# Pressure_Sensor_Breakout_Rev_2.net
KiCad netlist of a schematic drawn in Altium Designer
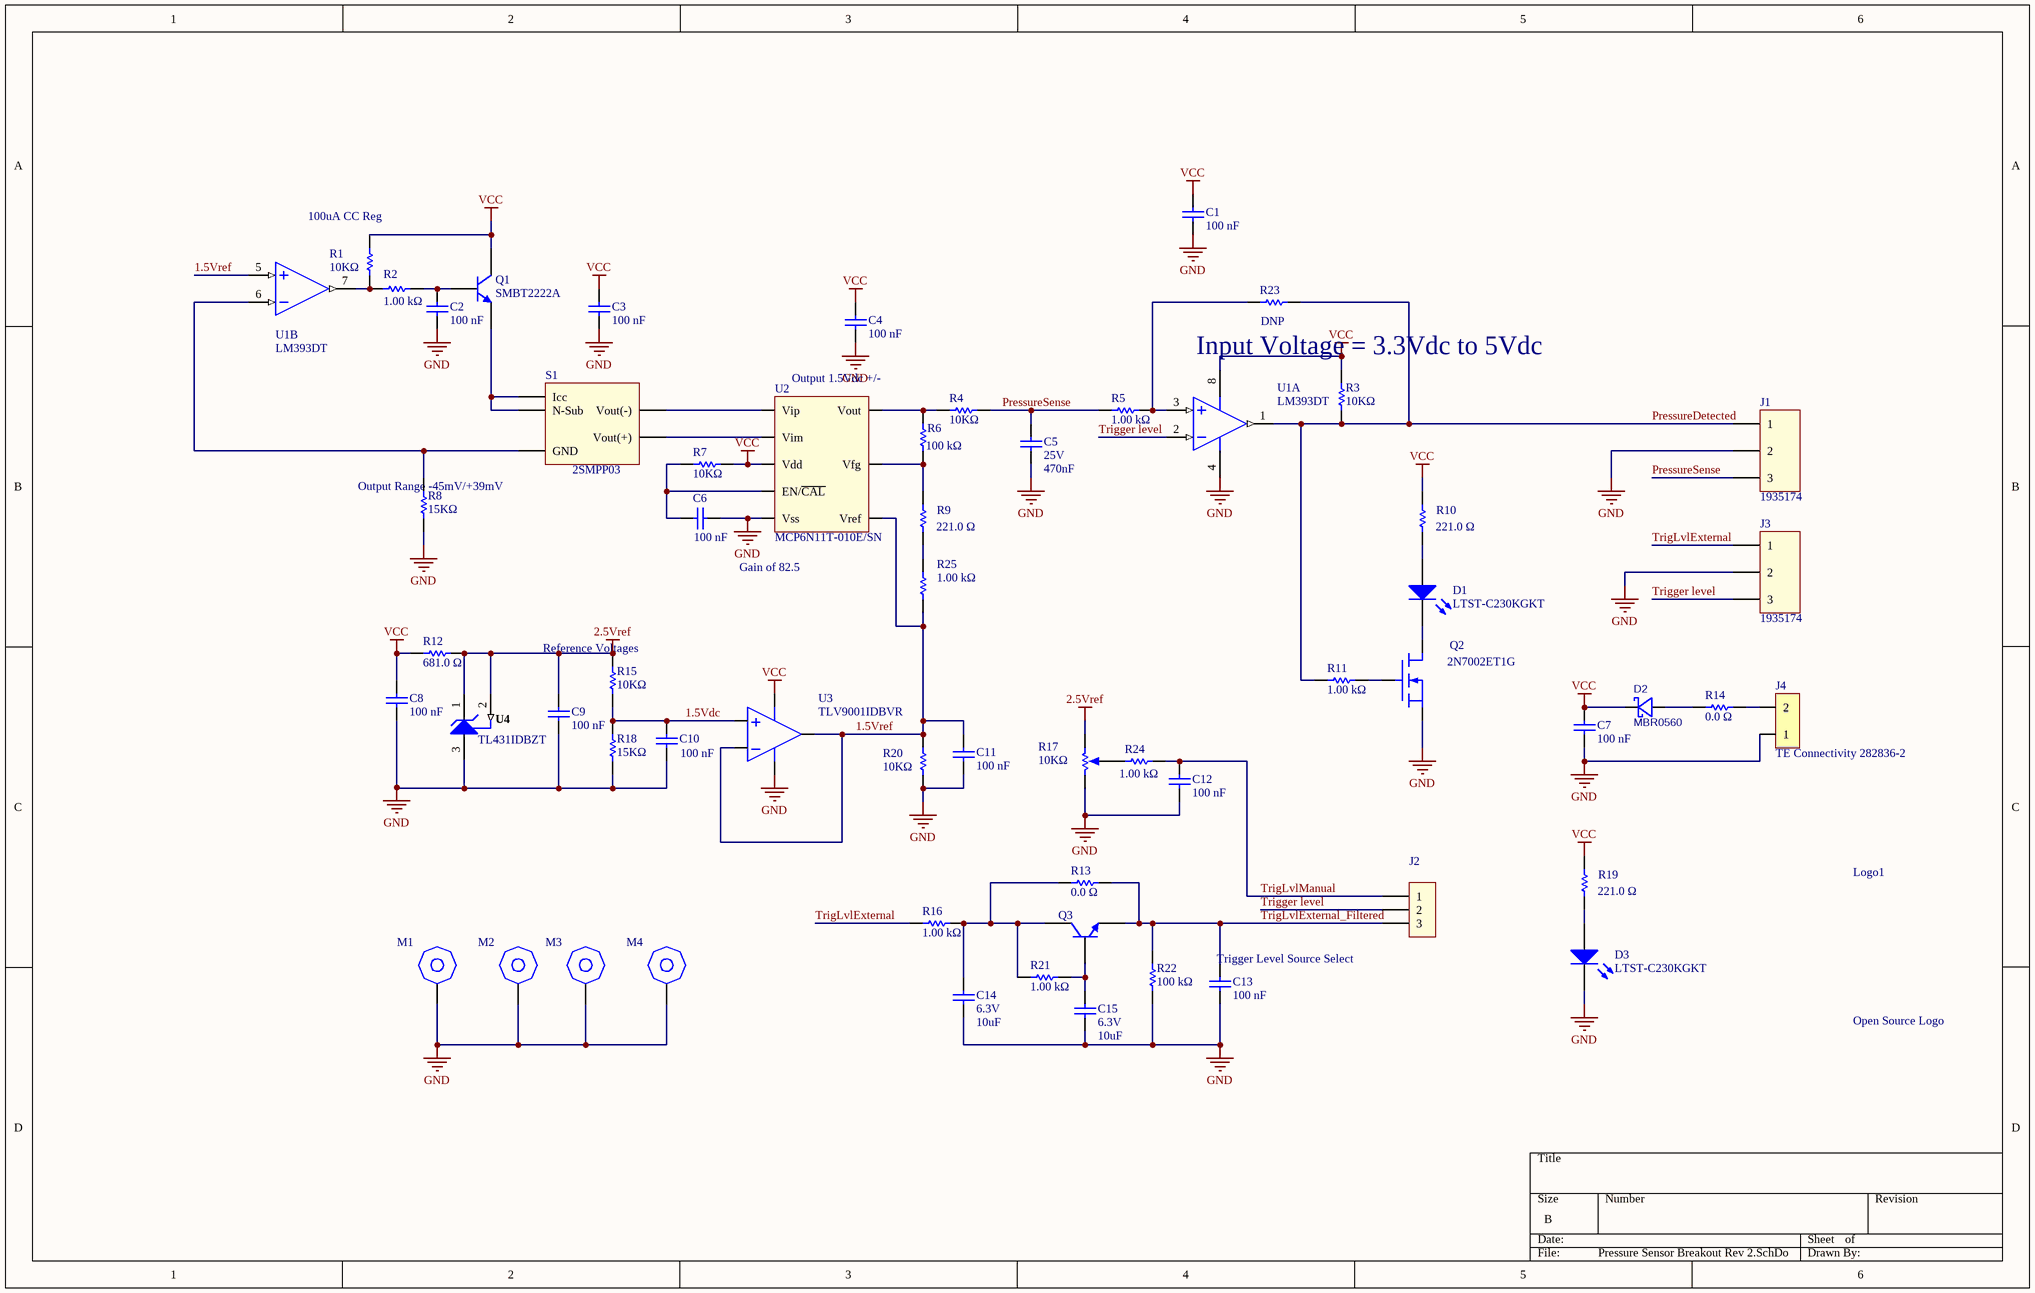
[diagram p0: Pressure Sensor Breakout Rev 2.SchDoc]

(export (version "E")
  (design (tool "Eeschema 10.0.6"))
  (components
    (comp (ref "C1")
      (value "08055C104JAT2A")
      (footprint "Cap,0805")
      (description "Capacitor; Ceramic; Cap 0.1 uF; Tol 5%; Vol-Rtg 50 VDC; SMT; 0805; X7R; Tape & Reel")
      (fields (field (name "CAPACITANCE") "100 nF"))
      (libsource (lib "Master JULY2019") (part "Cap,0805,100nf,50V,5%,08055C104JAT2A"))
    )
    (comp (ref "C2")
      (value "08055C104JAT2A")
      (footprint "Cap,0805")
      (description "Capacitor; Ceramic; Cap 0.1 uF; Tol 5%; Vol-Rtg 50 VDC; SMT; 0805; X7R; Tape & Reel")
      (fields (field (name "CAPACITANCE") "100 nF"))
      (libsource (lib "Master JULY2019") (part "Cap,0805,100nf,50V,5%,08055C104JAT2A"))
    )
    (comp (ref "C3")
      (value "08055C104JAT2A")
      (footprint "Cap,0805")
      (description "Capacitor; Ceramic; Cap 0.1 uF; Tol 5%; Vol-Rtg 50 VDC; SMT; 0805; X7R; Tape & Reel")
      (fields (field (name "CAPACITANCE") "100 nF"))
      (libsource (lib "Master JULY2019") (part "Cap,0805,100nf,50V,5%,08055C104JAT2A"))
    )
    (comp (ref "C4")
      (value "08055C104JAT2A")
      (footprint "Cap,0805")
      (description "Capacitor; Ceramic; Cap 0.1 uF; Tol 5%; Vol-Rtg 50 VDC; SMT; 0805; X7R; Tape & Reel")
      (fields (field (name "CAPACITANCE") "100 nF"))
      (libsource (lib "Master JULY2019") (part "Cap,0805,100nf,50V,5%,08055C104JAT2A"))
    )
    (comp (ref "C5")
      (value "CGA4J2X7R1E474K125AA")
      (footprint "Cap,0805")
      (description "0.47µF ±10% 25V Ceramic Capacitor X7R 0805 (2012 Metric)")
      (fields
        (field (name "MANUFACTURER") "TDK Corporation")
        (field (name "VOLTAGE RATING (DC)") "25V")
        (field (name "CAPACITANCE") "470nF")
      )
      (libsource (lib "Master Nov2021") (part "Cap,0805,470nf,25V,10%,CGA4J2X7R1E474K125AA"))
    )
    (comp (ref "C6")
      (value "08055C104JAT2A")
      (footprint "Cap,0805")
      (description "Capacitor; Ceramic; Cap 0.1 uF; Tol 5%; Vol-Rtg 50 VDC; SMT; 0805; X7R; Tape & Reel")
      (fields (field (name "CAPACITANCE") "100 nF"))
      (libsource (lib "Master JULY2019") (part "Cap,0805,100nf,50V,5%,08055C104JAT2A"))
    )
    (comp (ref "C7")
      (value "08055C104JAT2A")
      (footprint "Cap,0805")
      (description "Capacitor; Ceramic; Cap 0.1 uF; Tol 5%; Vol-Rtg 50 VDC; SMT; 0805; X7R; Tape & Reel")
      (fields (field (name "CAPACITANCE") "100 nF"))
      (libsource (lib "Master JULY2019") (part "Cap,0805,100nf,50V,5%,08055C104JAT2A"))
    )
    (comp (ref "C8")
      (value "08055C104JAT2A")
      (footprint "Cap,0805")
      (description "Capacitor; Ceramic; Cap 0.1 uF; Tol 5%; Vol-Rtg 50 VDC; SMT; 0805; X7R; Tape & Reel")
      (fields (field (name "CAPACITANCE") "100 nF"))
      (libsource (lib "Master JULY2019") (part "Cap,0805,100nf,50V,5%,08055C104JAT2A"))
    )
    (comp (ref "C9")
      (value "08055C104JAT2A")
      (footprint "Cap,0805")
      (description "Capacitor; Ceramic; Cap 0.1 uF; Tol 5%; Vol-Rtg 50 VDC; SMT; 0805; X7R; Tape & Reel")
      (fields (field (name "CAPACITANCE") "100 nF"))
      (libsource (lib "Master JULY2019") (part "Cap,0805,100nf,50V,5%,08055C104JAT2A"))
    )
    (comp (ref "C10")
      (value "08055C104JAT2A")
      (footprint "Cap,0805")
      (description "Capacitor; Ceramic; Cap 0.1 uF; Tol 5%; Vol-Rtg 50 VDC; SMT; 0805; X7R; Tape & Reel")
      (fields (field (name "CAPACITANCE") "100 nF"))
      (libsource (lib "Master JULY2019") (part "Cap,0805,100nf,50V,5%,08055C104JAT2A"))
    )
    (comp (ref "C11")
      (value "08055C104JAT2A")
      (footprint "Cap,0805")
      (description "Capacitor; Ceramic; Cap 0.1 uF; Tol 5%; Vol-Rtg 50 VDC; SMT; 0805; X7R; Tape & Reel")
      (fields (field (name "CAPACITANCE") "100 nF"))
      (libsource (lib "Master JULY2019") (part "Cap,0805,100nf,50V,5%,08055C104JAT2A"))
    )
    (comp (ref "C12")
      (value "08055C104JAT2A")
      (footprint "Cap,0805")
      (description "Capacitor; Ceramic; Cap 0.1 uF; Tol 5%; Vol-Rtg 50 VDC; SMT; 0805; X7R; Tape & Reel")
      (fields (field (name "CAPACITANCE") "100 nF"))
      (libsource (lib "Master JULY2019") (part "Cap,0805,100nf,50V,5%,08055C104JAT2A"))
    )
    (comp (ref "C13")
      (value "08055C104JAT2A")
      (footprint "Cap,0805")
      (description "Capacitor; Ceramic; Cap 0.1 uF; Tol 5%; Vol-Rtg 50 VDC; SMT; 0805; X7R; Tape & Reel")
      (fields (field (name "CAPACITANCE") "100 nF"))
      (libsource (lib "Master JULY2019") (part "Cap,0805,100nf,50V,5%,08055C104JAT2A"))
    )
    (comp (ref "C14")
      (value "Cap")
      (footprint "Cap,0805")
      (description "CL21 Series 10 uF 6.3V ±10 % Tolerance X5R SMT Multilayer Ceramic Capacitor")
      (fields
        (field (name "TOLERANCE") "±10%")
        (field (name "VOLTAGE - RATED") "6.3V")
        (field (name "CAPACITANCE") "10uF")
      )
      (libsource (lib "Master JUL_2019-Shawn") (part "Cap,0805,10uf,6.3V,10%,CL21A106KQFNNNG"))
    )
    (comp (ref "C15")
      (value "Cap")
      (footprint "Cap,0805")
      (description "CL21 Series 10 uF 6.3V ±10 % Tolerance X5R SMT Multilayer Ceramic Capacitor")
      (fields
        (field (name "TOLERANCE") "±10%")
        (field (name "VOLTAGE - RATED") "6.3V")
        (field (name "CAPACITANCE") "10uF")
      )
      (libsource (lib "Master JUL_2019-Shawn") (part "Cap,0805,10uf,6.3V,10%,CL21A106KQFNNNG"))
    )
    (comp (ref "D1")
      (value "LTST-C230KGKT")
      (footprint "LED,SMD,Bottom Entry,1206")
      (description "LED GREEN CLEAR CHIP SMD")
      (fields (field (name "MANUFACTURER") "Lite-On Inc."))
      (libsource (lib "Master DEC 2020") (part "LED,1206,Green,SMD,BtmEnt,LTST-C230KGKT"))
    )
    (comp (ref "D2")
      (value "MBR0560")
      (footprint "SOD123")
      (description "Dio,Sig,Schtky,0.5A,60V,SOD123")
      (fields (field (name "MANUFACTURER") "MCC") (field (name "VOLTAGE") "60V"))
      (libsource (lib "Master DEC 2020") (part "Diode,SOD123,Shottky,60V,0.5A,MBR0560"))
    )
    (comp (ref "D3")
      (value "LTST-C230KGKT")
      (footprint "LED,SMD,Bottom Entry,1206")
      (description "LED GREEN CLEAR CHIP SMD")
      (fields (field (name "MANUFACTURER") "Lite-On Inc."))
      (libsource (lib "Master DEC 2020") (part "LED,1206,Green,SMD,BtmEnt,LTST-C230KGKT"))
    )
    (comp (ref "J1")
      (value "1935174")
      (footprint "CONNECTOR,TerminalBlock,3 POS,1935174")
      (description "TERM BLK 3POS SIDE ENTRY 5MM PCB")
      (fields
        (field (name "MANUFACTURER") "Phoenix Contact")
        (field (name "VOLTAGE") "300V")
        (field (name "MFG P/N") "1935174")
      )
      (libsource (lib "Master DEC 2020") (part "Conn,TH,WireTerminal,3Pos,18A,300Vdc,1935174"))
    )
    (comp (ref "J2")
      (value "Generic Header")
      (footprint "Header,3POS,0.1\",Vert")
      (description "Generic Header 3 pos header 0.1\"")
      (libsource (lib "Master JULY2019") (part "Header 1x3,0.1{dblquote},TH,Generic"))
    )
    (comp (ref "J3")
      (value "1935174")
      (footprint "CONNECTOR,TerminalBlock,3 POS,1935174")
      (description "TERM BLK 3POS SIDE ENTRY 5MM PCB")
      (fields
        (field (name "MANUFACTURER") "Phoenix Contact")
        (field (name "VOLTAGE") "300V")
        (field (name "MFG P/N") "1935174")
      )
      (libsource (lib "Master DEC 2020") (part "Conn,TH,WireTerminal,3Pos,18A,300Vdc,1935174"))
    )
    (comp (ref "J4")
      (value "TE Connectivity 282836-2")
      (footprint "TERM BLOCK 2POS SIDE ENTRY 5MM")
      (description "Wire to Board 2 Position 5 mm Pitch 30-16 AWG Euro Style Terminal Block")
      (fields (field (name "MANUFACTURER PART NUMBER") "282836-2"))
      (libsource (lib "Master DEC 2020") (part "TERM BLOCK 2POS SIDE ENTRY 5MM, 282836-2"))
    )
    (comp (ref "Logo1")
      (value "Open Source Logo")
      (footprint "Symbol,Open Source")
      (description "Open Source Silk Screen Logo")
      (libsource (lib "Master Nov2021") (part "Symbol,Open Source"))
    )
    (comp (ref "M1")
      (value "M3 hex Standoff")
      (footprint "Standoff,Hex,M3,8mm")
      (description "HEX STANDOFF M3,generic")
      (libsource (lib "Master JULY2019") (part "Mech,Standoff, M3, Hex"))
    )
    (comp (ref "M2")
      (value "M3 hex Standoff")
      (footprint "Standoff,Hex,M3,8mm")
      (description "HEX STANDOFF M3,generic")
      (libsource (lib "Master JULY2019") (part "Mech,Standoff, M3, Hex"))
    )
    (comp (ref "M3")
      (value "M3 hex Standoff")
      (footprint "Standoff,Hex,M3,8mm")
      (description "HEX STANDOFF M3,generic")
      (libsource (lib "Master JULY2019") (part "Mech,Standoff, M3, Hex"))
    )
    (comp (ref "M4")
      (value "M3 hex Standoff")
      (footprint "Standoff,Hex,M3,8mm")
      (description "HEX STANDOFF M3,generic")
      (libsource (lib "Master JULY2019") (part "Mech,Standoff, M3, Hex"))
    )
    (comp (ref "Q1")
      (value "SMBT2222A")
      (footprint "SOT23-3")
      (description "NPN Silicon Switching Transistor, 40 V VCEO, 600 mA IC, SOT23, Reel, Green")
      (fields (field (name "MFG P/N") "SMBT2222A"))
      (libsource (lib "Master JULY2019") (part "Trans,40V,600mA,0.33W, SMBT2222A"))
    )
    (comp (ref "Q2")
      (value "2N7002ET1G")
      (footprint "SOT23-3")
      (description "Small Signal MOSFET, 60 V, 310 mA, Single, N-Channel, 3-Pin SOT-23, Pb-Free, Tape and Reel")
      (fields
        (field (name "MANUFACTURER") "ON Semiconductor")
        (field (name "MANUFACTURER PART NUMBER") "2N7002ET1G")
      )
      (libsource (lib "Master DEC 2020") (part "MOSFET,N-Channel,SOT23,0.25A,60V,2N7002ET1G"))
    )
    (comp (ref "Q3")
      (value "NPN")
      (footprint "SOT23-3")
      (description "NPN Silicon Switching Transistor, 40 V VCEO, 600 mA IC, SOT23, Reel, Green")
      (libsource (lib "Master JUL_2019-Shawn") (part "Trans,40V,600mA,0.33W, SMBT2222A"))
    )
    (comp (ref "R1")
      (value "Vishay / Dale CRCW080510K0FKTA")
      (footprint "res, 0805, HD")
      (description "RES SMD 10K OHM 1% 1/8W 0805")
      (fields (field (name "RESISTANCE") "10KΩ"))
      (libsource (lib "Master JULY2019") (part "Res,0805,10.0kΩ,1%,100 ppm,CRCW080510K0FKTA"))
    )
    (comp (ref "R2")
      (value "Vishay CRCW08051K00JNEA")
      (footprint "res, 0805, HD")
      (description "Res Thick Film 0805 1K Ohm 5% 0.125W(1/8W) ±200ppm/C Molded SMD Automotive Paper T/R")
      (fields
        (field (name "MANUFACTURER PART NUMBER") "CRCW08051K00JNEA")
        (field (name "RESISTANCE") "1.00 kΩ")
      )
      (libsource (lib "Master JULY2019") (part "Res,0805,1.00 kΩ,5%,200ppm,CRCW08051K00JNEA"))
    )
    (comp (ref "R3")
      (value "Vishay / Dale CRCW080510K0FKTA")
      (footprint "res, 0805, HD")
      (description "RES SMD 10K OHM 1% 1/8W 0805")
      (fields (field (name "RESISTANCE") "10KΩ"))
      (libsource (lib "Master JULY2019") (part "Res,0805,10.0kΩ,1%,100 ppm,CRCW080510K0FKTA"))
    )
    (comp (ref "R4")
      (value "Vishay / Dale CRCW080510K0FKTA")
      (footprint "res, 0805, HD")
      (description "RES SMD 10K OHM 1% 1/8W 0805")
      (fields (field (name "RESISTANCE") "10KΩ"))
      (libsource (lib "Master DEC 2020") (part "Res,0805,10.0kΩ,1%,100 ppm,CRCW080510K0FKTA"))
    )
    (comp (ref "R5")
      (value "Vishay CRCW08051K00JNEA")
      (footprint "res, 0805, HD")
      (description "Res Thick Film 0805 1K Ohm 5% 0.125W(1/8W) ±200ppm/C Molded SMD Automotive Paper T/R")
      (fields
        (field (name "MANUFACTURER PART NUMBER") "CRCW08051K00JNEA")
        (field (name "RESISTANCE") "1.00 kΩ")
      )
      (libsource (lib "Master JULY2019") (part "Res,0805,1.00 kΩ,5%,200ppm,CRCW08051K00JNEA"))
    )
    (comp (ref "R6")
      (value "CRCW0805100KFKEA")
      (footprint "res, 0805, HD")
      (description "100 kOhms ±1% 0.125W, 1/8W Chip Resistor 0805 (2012 Metric) Thick Film")
      (fields (field (name "MANUFACTURER") "Vishay") (field (name "RESISTANCE") "100 kΩ"))
      (libsource (lib "Master DEC 2020") (part "Res,0805,100kΩ,1%,100ppm,CRCW0805100KFKEA"))
    )
    (comp (ref "R7")
      (value "Vishay / Dale CRCW080510K0FKTA")
      (footprint "res, 0805, HD")
      (description "RES SMD 10K OHM 1% 1/8W 0805")
      (fields (field (name "RESISTANCE") "10KΩ"))
      (libsource (lib "Master JULY2019") (part "Res,0805,10.0kΩ,1%,100 ppm,CRCW080510K0FKTA"))
    )
    (comp (ref "R8")
      (value "CRGCQ0805F15K")
      (footprint "res, 0805, HD")
      (fields (field (name "TOLERANCE") "±1%") (field (name "RESISTANCE") "15KΩ"))
      (libsource (lib "Master JULY2019") (part "Res,0805,15KΩ,1%,±100ppm/°C,CRGCQ0805F15K"))
    )
    (comp (ref "R9")
      (value "Vishay Dale CRCW0805221RFKTA")
      (footprint "res, 0805, HD")
      (description "RES SMD 221 OHM 1% 1/8W 0805")
      (fields (field (name "RESISTANCE") "221.0 Ω"))
      (libsource (lib "Master DEC 2020") (part "Res,0805,221Ω,1%,100ppm,CRCW0805221RFKTA"))
    )
    (comp (ref "R10")
      (value "Vishay Dale CRCW0805221RFKTA")
      (footprint "res, 0805, HD")
      (description "RES SMD 221 OHM 1% 1/8W 0805")
      (fields (field (name "RESISTANCE") "221.0 Ω"))
      (libsource (lib "Master DEC 2020") (part "Res,0805,221Ω,1%,100ppm,CRCW0805221RFKTA"))
    )
    (comp (ref "R11")
      (value "Vishay CRCW08051K00JNEA")
      (footprint "res, 0805, HD")
      (description "Res Thick Film 0805 1K Ohm 5% 0.125W(1/8W) ±200ppm/C Molded SMD Automotive Paper T/R")
      (fields
        (field (name "MANUFACTURER PART NUMBER") "CRCW08051K00JNEA")
        (field (name "RESISTANCE") "1.00 kΩ")
      )
      (libsource (lib "Master JULY2019") (part "Res,0805,1.00 kΩ,5%,200ppm,CRCW08051K00JNEA"))
    )
    (comp (ref "R12")
      (value "CRCW0805681RFKEA")
      (footprint "res, 0805, HD")
      (description "RES SMD 681 OHM 1% 1/8W 0805")
      (fields (field (name "RESISTANCE") "681.0 Ω"))
      (libsource (lib "Master JULY2019") (part "Res,0805,681.0 Ω,±1%,100.0 ppm/°C,150.0 V,CRCW0805681RFKEA"))
    )
    (comp (ref "R13")
      (value "Res1")
      (footprint "res, 0805, HD")
      (description "RES SMD 0.0 OHM JUMPER 1/3W 0805")
      (fields (field (name "RESISTANCE") "0.0 Ω"))
      (libsource (lib "Master JULY2019") (part "Res,0805,0.0Ω,150V"))
    )
    (comp (ref "R14")
      (value "CR0805-J/-000ELF")
      (footprint "res, 0805, HD")
      (description "RES SMD 0 OHM JUMPER 1/8W 0805")
      (fields
        (field (name "TOLERANCE") "Jumper")
        (field (name "BASE PART NUMBER") "CR0805")
        (field (name "RESISTANCE") "0.0 Ω")
      )
      (libsource (lib "Master DEC 2020") (part "Res,0805,0.0Ω,150V, CR0805-J/-000ELF"))
    )
    (comp (ref "R15")
      (value "Vishay / Dale CRCW080510K0FKTA")
      (footprint "res, 0805, HD")
      (description "RES SMD 10K OHM 1% 1/8W 0805")
      (fields (field (name "RESISTANCE") "10KΩ"))
      (libsource (lib "Master JULY2019") (part "Res,0805,10.0kΩ,1%,100 ppm,CRCW080510K0FKTA"))
    )
    (comp (ref "R16")
      (value "Vishay CRCW08051K00JNEA")
      (footprint "res, 0805, HD")
      (description "Res Thick Film 0805 1K Ohm 5% 0.125W(1/8W) ±200ppm/C Molded SMD Automotive Paper T/R")
      (fields
        (field (name "MANUFACTURER PART NUMBER") "CRCW08051K00JNEA")
        (field (name "RESISTANCE") "1.00 kΩ")
      )
      (libsource (lib "Master JULY2019") (part "Res,0805,1.00 kΩ,5%,200ppm,CRCW08051K00JNEA"))
    )
    (comp (ref "R17")
      (value "TC33X-2-103E")
      (footprint "Res,SMD,POT,TC33 Series")
      (description "TRIMMER 10K OHM 0.1W J LEAD TOP")
      (fields
        (field (name "MANUFACTURER") "Bourns Inc.")
        (field (name "TOLERANCE") "±25%")
        (field (name "RESISTANCE") "10KΩ")
      )
      (libsource (lib "Master Nov2021") (part "Res,POT,SMD,10KΩ,0.1W, TC33X-2-103E"))
    )
    (comp (ref "R18")
      (value "CRGCQ0805F15K")
      (footprint "res, 0805, HD")
      (fields (field (name "TOLERANCE") "±1%") (field (name "RESISTANCE") "15KΩ"))
      (libsource (lib "Master JULY2019") (part "Res,0805,15KΩ,1%,±100ppm/°C,CRGCQ0805F15K"))
    )
    (comp (ref "R19")
      (value "Vishay Dale CRCW0805221RFKTA")
      (footprint "res, 0805, HD")
      (description "RES SMD 221 OHM 1% 1/8W 0805")
      (fields (field (name "RESISTANCE") "221.0 Ω"))
      (libsource (lib "Master DEC 2020") (part "Res,0805,221Ω,1%,100ppm,CRCW0805221RFKTA"))
    )
    (comp (ref "R20")
      (value "Vishay / Dale CRCW080510K0FKTA")
      (footprint "res, 0805, HD")
      (description "RES SMD 10K OHM 1% 1/8W 0805")
      (fields (field (name "RESISTANCE") "10KΩ"))
      (libsource (lib "Master JULY2019") (part "Res,0805,10.0kΩ,1%,100 ppm,CRCW080510K0FKTA"))
    )
    (comp (ref "R21")
      (value "Vishay CRCW08051K00JNEA")
      (footprint "res, 0805, HD")
      (description "Res Thick Film 0805 1K Ohm 5% 0.125W(1/8W) ±200ppm/C Molded SMD Automotive Paper T/R")
      (fields
        (field (name "MANUFACTURER PART NUMBER") "CRCW08051K00JNEA")
        (field (name "RESISTANCE") "1.00 kΩ")
      )
      (libsource (lib "Master JULY2019") (part "Res,0805,1.00 kΩ,5%,200ppm,CRCW08051K00JNEA"))
    )
    (comp (ref "R22")
      (value "Res,0805,100kΩ,1%,100ppm,CRCW0805100KFKEA")
      (footprint "res, 0805, HD")
      (description "100 kOhms ±1% 0.125W, 1/8W Chip Resistor 0805 (2012 Metric) Thick Film")
      (fields
        (field (name "MANUFACTURER PART NUMBER") "CRCW0805100KFKEA")
        (field (name "MANUFACTURER") "Vishay")
        (field (name "RESISTANCE") "100 kΩ")
      )
      (libsource (lib "Master JULY2019") (part "Res,0805,100kΩ,1%,100ppm,CRCW0805100KFKEA"))
    )
    (comp (ref "R23")
      (value "CR0805-JW-105ELF")
      (footprint "res, 0805, HD")
      (description "RES SMD 1M OHM 5% 1/8W 0805")
      (fields
        (field (name "MANUFACTURER") "Bourns Inc.")
        (field (name "JLC ALT LCSC PART #") "C26108")
        (field (name "RESISTANCE") "DNP")
      )
      (libsource (lib "Master JULY2019") (part "Res,0805,1MegΩ,5%,200ppm,0805W8F1005T5E"))
    )
    (comp (ref "R24")
      (value "Vishay CRCW08051K00JNEA")
      (footprint "res, 0805, HD")
      (description "Res Thick Film 0805 1K Ohm 5% 0.125W(1/8W) ±200ppm/C Molded SMD Automotive Paper T/R")
      (fields
        (field (name "MANUFACTURER PART NUMBER") "CRCW08051K00JNEA")
        (field (name "RESISTANCE") "1.00 kΩ")
      )
      (libsource (lib "Master JULY2019") (part "Res,0805,1.00 kΩ,5%,200ppm,CRCW08051K00JNEA"))
    )
    (comp (ref "R25")
      (value "Vishay CRCW08051K00JNEA")
      (footprint "res, 0805, HD")
      (description "Res Thick Film 0805 1K Ohm 5% 0.125W(1/8W) ±200ppm/C Molded SMD Automotive Paper T/R")
      (fields
        (field (name "MANUFACTURER PART NUMBER") "CRCW08051K00JNEA")
        (field (name "RESISTANCE") "1.00 kΩ")
      )
      (libsource (lib "Master Nov2021") (part "Res,0805,1.00 kΩ,5%,200ppm,CRCW08051K00JNEA"))
    )
    (comp (ref "S1")
      (value "2SMPP03")
      (footprint "2SMPP03,6-SMD Module")
      (description "SENSOR PRESSURE -50-50 KPA PCB")
      (fields
        (field (name "MANUFACTURER") "Omron Electronics Inc-EMC Div")
        (field (name "MFG P/N") "2SMPP03")
      )
      (libsource (lib "Master JULY2019") (part "Sensor,PRESSURE,Air, ±7.25PSI, 2SMPP03"))
    )
    (comp (ref "U1")
      (value "LM393DT")
      (footprint "SOIC-8")
      (description "IC COMPARATOR LP DUAL 8-SOIC")
      (fields (field (name "MANUFACTURER") "STMicroelectronics") (field (name "BASE PART NUMBER") "LM393"))
      (libsource (lib "Master JULY2019") (part "OPAMP,DUAL,COMAPRATOR,SOIC8,OPEN-COLLECTOR,LM393DT"))
    )
    (comp (ref "U2")
      (value "MCP6N11T-010E/SN")
      (footprint "SOIC-8")
      (description "IC INST AMP 1 CIRCUIT 8SOIC")
      (fields
        (field (name "MFG P/N") "MCP6N11T-010E/SN")
        (field (name "MANUFACTURER") "Microchip Technology")
      )
      (libsource (lib "Master JULY2019") (part "Opamp,Instrumentation,SOIC,5Mhz,RailToRail, MCP6N11T-010E/SN"))
    )
    (comp (ref "U3")
      (value "TLV9001IDBVR")
      (footprint "SOT23-5")
      (description "IC CMOS 1 CIRCUIT SOT23-5")
      (fields (field (name "MFG P/N") "TLV9001IDBVR") (field (name "MANUFACTURER") "Texas Instruments"))
      (libsource (lib "Master JULY2019") (part "OPAMP,Single,1Mhz,RailToRail,SOT-5, TLV9001IDBVR"))
    )
    (comp (ref "U4")
      (value "Shunt Regulator,2.5Vdc TL431IDBZT")
      (footprint "SOT23-3")
      (fields (field (name "MANUFACTURER PART NUMBER") "TL431IDBZT"))
      (libsource (lib "Master JULY2019") (part "Shunt Regulator,2.5Vdc TL431IDBZT"))
    )
  )
  (nets
    (net (code "1") (name "/1.5Vdc") (class "Default")
      (node (ref "C10") (pin "1") (pinfunction "1_1") (pintype "passive"))
      (node (ref "R15") (pin "1") (pinfunction "1_1") (pintype "passive"))
      (node (ref "R18") (pin "2") (pinfunction "2_2") (pintype "passive"))
      (node (ref "U3") (pin "3") (pinfunction "IN+_3") (pintype "passive"))
    )
    (net (code "2") (name "/1.5Vref") (class "Default")
      (node (ref "C11") (pin "1") (pinfunction "1_1") (pintype "passive"))
      (node (ref "R20") (pin "2") (pinfunction "2_2") (pintype "passive"))
      (node (ref "R25") (pin "2") (pinfunction "2_2") (pintype "passive"))
      (node (ref "U1") (pin "5") (pinfunction "IN2+_5") (pintype "input"))
      (node (ref "U2") (pin "5") (pinfunction "Vref_5") (pintype "passive"))
      (node (ref "U3") (pin "1") (pinfunction "Out_1") (pintype "passive"))
      (node (ref "U3") (pin "4") (pinfunction "IN-_4") (pintype "passive"))
    )
    (net (code "3") (name "/PressureDetected") (class "Default")
      (node (ref "J1") (pin "1") (pinfunction "1_1") (pintype "passive"))
      (node (ref "R11") (pin "2") (pinfunction "2_2") (pintype "passive"))
      (node (ref "R23") (pin "1") (pinfunction "1_1") (pintype "passive"))
      (node (ref "R3") (pin "1") (pinfunction "1_1") (pintype "passive"))
      (node (ref "U1") (pin "1") (pinfunction "OUT1_1") (pintype "output"))
    )
    (net (code "4") (name "/PressureSense") (class "Default")
      (node (ref "C5") (pin "2") (pinfunction "2_2") (pintype "passive"))
      (node (ref "J1") (pin "3") (pinfunction "3_3") (pintype "passive"))
      (node (ref "R4") (pin "1") (pinfunction "1_1") (pintype "passive"))
      (node (ref "R5") (pin "1") (pinfunction "1_1") (pintype "passive"))
    )
    (net (code "5") (name "/TrigLvlExternal") (class "Default")
      (node (ref "J3") (pin "1") (pinfunction "1_1") (pintype "passive"))
      (node (ref "R16") (pin "1") (pinfunction "1_1") (pintype "passive"))
    )
    (net (code "6") (name "/TrigLvlExternal_Filtered") (class "Default")
      (node (ref "C13") (pin "1") (pinfunction "1_1") (pintype "passive"))
      (node (ref "J2") (pin "3") (pinfunction "3_3") (pintype "passive"))
      (node (ref "Q3") (pin "3") (pinfunction "E_3") (pintype "passive"))
      (node (ref "R13") (pin "1") (pinfunction "1_1") (pintype "passive"))
      (node (ref "R22") (pin "2") (pinfunction "2_2") (pintype "passive"))
    )
    (net (code "7") (name "/TrigLvlManual") (class "Default")
      (node (ref "C12") (pin "1") (pinfunction "1_1") (pintype "passive"))
      (node (ref "J2") (pin "1") (pinfunction "1_1") (pintype "passive"))
      (node (ref "R24") (pin "1") (pinfunction "1_1") (pintype "passive"))
    )
    (net (code "8") (name "/Trigger level") (class "Default")
      (node (ref "J2") (pin "2") (pinfunction "2_2") (pintype "passive"))
      (node (ref "J3") (pin "3") (pinfunction "3_3") (pintype "passive"))
      (node (ref "U1") (pin "2") (pinfunction "IN1-_2") (pintype "input"))
    )
    (net (code "9") (name "2.5Vref") (class "Default")
      (node (ref "C9") (pin "1") (pinfunction "1_1") (pintype "passive"))
      (node (ref "R12") (pin "1") (pinfunction "1_1") (pintype "passive"))
      (node (ref "R15") (pin "2") (pinfunction "2_2") (pintype "passive"))
      (node (ref "R17") (pin "3") (pinfunction "3_3") (pintype "passive"))
      (node (ref "U4") (pin "1") (pinfunction "CATHODE_1") (pintype "passive"))
      (node (ref "U4") (pin "2") (pinfunction "REF_2") (pintype "input"))
    )
    (net (code "10") (name "GND") (class "Default")
      (node (ref "C1") (pin "2") (pinfunction "2_2") (pintype "passive"))
      (node (ref "C10") (pin "2") (pinfunction "2_2") (pintype "passive"))
      (node (ref "C11") (pin "2") (pinfunction "2_2") (pintype "passive"))
      (node (ref "C12") (pin "2") (pinfunction "2_2") (pintype "passive"))
      (node (ref "C13") (pin "2") (pinfunction "2_2") (pintype "passive"))
      (node (ref "C14") (pin "1") (pinfunction "1_1") (pintype "passive"))
      (node (ref "C15") (pin "1") (pinfunction "1_1") (pintype "passive"))
      (node (ref "C2") (pin "2") (pinfunction "2_2") (pintype "passive"))
      (node (ref "C3") (pin "2") (pinfunction "2_2") (pintype "passive"))
      (node (ref "C4") (pin "2") (pinfunction "2_2") (pintype "passive"))
      (node (ref "C5") (pin "1") (pinfunction "1_1") (pintype "passive"))
      (node (ref "C6") (pin "1") (pinfunction "1_1") (pintype "passive"))
      (node (ref "C7") (pin "2") (pinfunction "2_2") (pintype "passive"))
      (node (ref "C8") (pin "2") (pinfunction "2_2") (pintype "passive"))
      (node (ref "C9") (pin "2") (pinfunction "2_2") (pintype "passive"))
      (node (ref "D3") (pin "1") (pinfunction "K_1") (pintype "passive"))
      (node (ref "J1") (pin "2") (pinfunction "2_2") (pintype "passive"))
      (node (ref "J3") (pin "2") (pinfunction "2_2") (pintype "passive"))
      (node (ref "J4") (pin "1") (pinfunction "1_1") (pintype "passive"))
      (node (ref "M1") (pin "0") (pinfunction "0_0") (pintype "passive"))
      (node (ref "M2") (pin "0") (pinfunction "0_0") (pintype "passive"))
      (node (ref "M3") (pin "0") (pinfunction "0_0") (pintype "passive"))
      (node (ref "M4") (pin "0") (pinfunction "0_0") (pintype "passive"))
      (node (ref "Q2") (pin "2") (pinfunction "S_2") (pintype "passive"))
      (node (ref "R17") (pin "1") (pinfunction "1_1") (pintype "passive"))
      (node (ref "R18") (pin "1") (pinfunction "1_1") (pintype "passive"))
      (node (ref "R20") (pin "1") (pinfunction "1_1") (pintype "passive"))
      (node (ref "R22") (pin "1") (pinfunction "1_1") (pintype "passive"))
      (node (ref "R8") (pin "1") (pinfunction "1_1") (pintype "passive"))
      (node (ref "U1") (pin "4") (pinfunction "Gnd_4") (pintype "power_in"))
      (node (ref "U2") (pin "4") (pinfunction "Vss_4") (pintype "passive"))
      (node (ref "U3") (pin "2") (pinfunction "V-_2") (pintype "passive"))
      (node (ref "U4") (pin "3") (pinfunction "ANODE_3") (pintype "passive"))
    )
    (net (code "11") (name "Net-(D1-A)") (class "Default")
      (node (ref "D1") (pin "2") (pinfunction "A_2") (pintype "passive"))
      (node (ref "R10") (pin "1") (pinfunction "1_1") (pintype "passive"))
    )
    (net (code "12") (name "Net-(D1-K)") (class "Default")
      (node (ref "D1") (pin "1") (pinfunction "K_1") (pintype "passive"))
      (node (ref "Q2") (pin "3") (pinfunction "D_3") (pintype "passive"))
    )
    (net (code "13") (name "Net-(D2-A)") (class "Default")
      (node (ref "D2") (pin "2") (pinfunction "A_2") (pintype "passive"))
      (node (ref "R14") (pin "2") (pinfunction "2_2") (pintype "passive"))
    )
    (net (code "14") (name "Net-(D3-A)") (class "Default")
      (node (ref "D3") (pin "2") (pinfunction "A_2") (pintype "passive"))
      (node (ref "R19") (pin "1") (pinfunction "1_1") (pintype "passive"))
    )
    (net (code "15") (name "Net-(J4-Pad2)") (class "Default")
      (node (ref "J4") (pin "2") (pinfunction "2_2") (pintype "passive"))
      (node (ref "R14") (pin "1") (pinfunction "1_1") (pintype "passive"))
    )
    (net (code "16") (name "Net-(Q1-B)") (class "Default")
      (node (ref "C2") (pin "1") (pinfunction "1_1") (pintype "passive"))
      (node (ref "Q1") (pin "1") (pinfunction "B_1") (pintype "passive"))
      (node (ref "R2") (pin "1") (pinfunction "1_1") (pintype "passive"))
    )
    (net (code "17") (name "Net-(Q1-E)") (class "Default")
      (node (ref "Q1") (pin "2") (pinfunction "E_2") (pintype "passive"))
      (node (ref "S1") (pin "5") (pinfunction "N-Sub_5") (pintype "passive"))
      (node (ref "S1") (pin "6") (pinfunction "Icc_6") (pintype "passive"))
    )
    (net (code "18") (name "Net-(Q2-G)") (class "Default")
      (node (ref "Q2") (pin "1") (pinfunction "G_1") (pintype "passive"))
      (node (ref "R11") (pin "1") (pinfunction "1_1") (pintype "passive"))
    )
    (net (code "19") (name "Net-(Q3-B)") (class "Default")
      (node (ref "C15") (pin "2") (pinfunction "2_2") (pintype "passive"))
      (node (ref "Q3") (pin "2") (pinfunction "B_2") (pintype "passive"))
      (node (ref "R21") (pin "1") (pinfunction "1_1") (pintype "passive"))
    )
    (net (code "20") (name "Net-(Q3-C)") (class "Default")
      (node (ref "C14") (pin "2") (pinfunction "2_2") (pintype "passive"))
      (node (ref "Q3") (pin "1") (pinfunction "C_1") (pintype "passive"))
      (node (ref "R13") (pin "2") (pinfunction "2_2") (pintype "passive"))
      (node (ref "R16") (pin "2") (pinfunction "2_2") (pintype "passive"))
      (node (ref "R21") (pin "2") (pinfunction "2_2") (pintype "passive"))
    )
    (net (code "21") (name "Net-(R17-Pad2)") (class "Default")
      (node (ref "R17") (pin "2") (pinfunction "2_2") (pintype "passive"))
      (node (ref "R24") (pin "2") (pinfunction "2_2") (pintype "passive"))
    )
    (net (code "22") (name "Net-(R25-Pad1)") (class "Default")
      (node (ref "R25") (pin "1") (pinfunction "1_1") (pintype "passive"))
      (node (ref "R9") (pin "1") (pinfunction "1_1") (pintype "passive"))
    )
    (net (code "23") (name "Net-(S1-GND)") (class "Default")
      (node (ref "R8") (pin "2") (pinfunction "2_2") (pintype "passive"))
      (node (ref "S1") (pin "3") (pinfunction "GND_3") (pintype "passive"))
      (node (ref "U1") (pin "6") (pinfunction "IN2-_6") (pintype "input"))
    )
    (net (code "24") (name "Net-(S1-Vout(+))") (class "Default")
      (node (ref "S1") (pin "1") (pinfunction "Vout(+)_1") (pintype "passive"))
      (node (ref "U2") (pin "2") (pinfunction "Vim_2") (pintype "passive"))
    )
    (net (code "25") (name "Net-(S1-Vout(-))") (class "Default")
      (node (ref "S1") (pin "4") (pinfunction "Vout(-)_4") (pintype "passive"))
      (node (ref "U2") (pin "3") (pinfunction "Vip_3") (pintype "passive"))
    )
    (net (code "26") (name "Net-(U1A-IN1+)") (class "Default")
      (node (ref "R23") (pin "2") (pinfunction "2_2") (pintype "passive"))
      (node (ref "R5") (pin "2") (pinfunction "2_2") (pintype "passive"))
      (node (ref "U1") (pin "3") (pinfunction "IN1+_3") (pintype "input"))
    )
    (net (code "27") (name "Net-(U1B-OUT2)") (class "Default")
      (node (ref "R1") (pin "1") (pinfunction "1_1") (pintype "passive"))
      (node (ref "R2") (pin "2") (pinfunction "2_2") (pintype "passive"))
      (node (ref "U1") (pin "7") (pinfunction "OUT2_7") (pintype "output"))
    )
    (net (code "28") (name "Net-(U2-EN{slash}~{CAL})") (class "Default")
      (node (ref "C6") (pin "2") (pinfunction "2_2") (pintype "passive"))
      (node (ref "R7") (pin "1") (pinfunction "1_1") (pintype "passive"))
      (node (ref "U2") (pin "8") (pinfunction "EN/~{CAL}_8") (pintype "passive"))
    )
    (net (code "29") (name "Net-(U2-Vfg)") (class "Default")
      (node (ref "R6") (pin "1") (pinfunction "1_1") (pintype "passive"))
      (node (ref "R9") (pin "2") (pinfunction "2_2") (pintype "passive"))
      (node (ref "U2") (pin "1") (pinfunction "Vfg_1") (pintype "passive"))
    )
    (net (code "30") (name "Net-(U2-Vout)") (class "Default")
      (node (ref "R4") (pin "2") (pinfunction "2_2") (pintype "passive"))
      (node (ref "R6") (pin "2") (pinfunction "2_2") (pintype "passive"))
      (node (ref "U2") (pin "6") (pinfunction "Vout_6") (pintype "passive"))
    )
    (net (code "31") (name "VCC") (class "Default")
      (node (ref "C1") (pin "1") (pinfunction "1_1") (pintype "passive"))
      (node (ref "C3") (pin "1") (pinfunction "1_1") (pintype "passive"))
      (node (ref "C4") (pin "1") (pinfunction "1_1") (pintype "passive"))
      (node (ref "C7") (pin "1") (pinfunction "1_1") (pintype "passive"))
      (node (ref "C8") (pin "1") (pinfunction "1_1") (pintype "passive"))
      (node (ref "D2") (pin "1") (pinfunction "C_1") (pintype "passive"))
      (node (ref "Q1") (pin "3") (pinfunction "C_3") (pintype "passive"))
      (node (ref "R1") (pin "2") (pinfunction "2_2") (pintype "passive"))
      (node (ref "R10") (pin "2") (pinfunction "2_2") (pintype "passive"))
      (node (ref "R12") (pin "2") (pinfunction "2_2") (pintype "passive"))
      (node (ref "R19") (pin "2") (pinfunction "2_2") (pintype "passive"))
      (node (ref "R3") (pin "2") (pinfunction "2_2") (pintype "passive"))
      (node (ref "R7") (pin "2") (pinfunction "2_2") (pintype "passive"))
      (node (ref "U1") (pin "8") (pinfunction "Vcc_8") (pintype "power_in"))
      (node (ref "U2") (pin "7") (pinfunction "Vdd_7") (pintype "passive"))
      (node (ref "U3") (pin "5") (pinfunction "V+_5") (pintype "passive"))
    )
    (net (code "32") (name "unconnected-(S1-NC-Pad2)") (class "Default")
      (node (ref "S1") (pin "2") (pinfunction "NC_2") (pintype "passive"))
    )
  )
)
